# drivercontrols_adafruit_M0.net
KiCad netlist of a schematic drawn in EAGLE
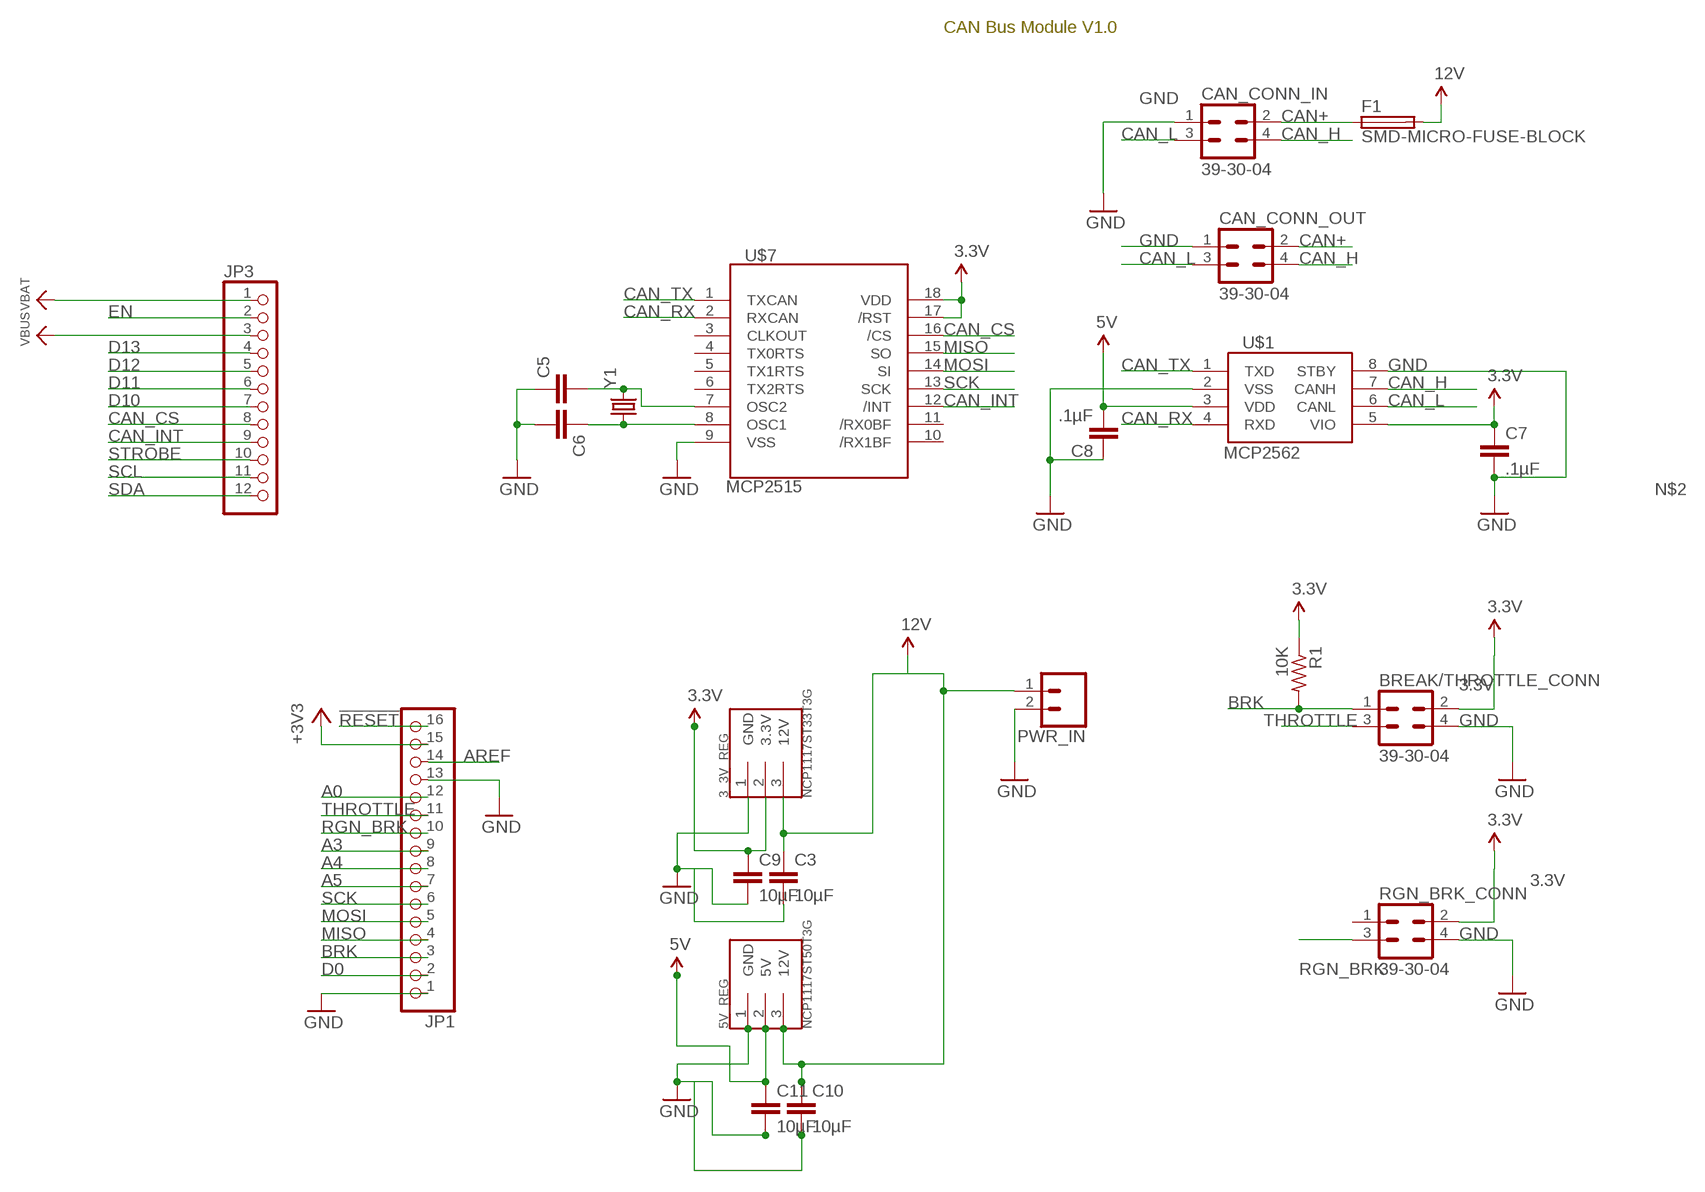
[diagram p0: schematic, sheet 1]

(export (version "E")
  (design (tool "Eeschema 10.0.6"))
  (components
    (comp (ref "3_3V_REG")
      (value "NCP1117ST33T3G")
      (footprint "eagle-import:SOT223")
      (libsource (lib "eagle-import") (part "NCP1117ST33T3G"))
    )
    (comp (ref "5V_REG")
      (value "NCP1117ST50T3G")
      (footprint "eagle-import:SOT223")
      (libsource (lib "eagle-import") (part "NCP1117ST50T3G"))
    )
    (comp (ref "BREAK/THROTTLE_CONN")
      (value "39-30-04")
      (footprint "eagle-import:39-30-_04_")
      (libsource (lib "eagle-import") (part "39-30-?04?"))
    )
    (comp (ref "C3")
      (value "10µF")
      (footprint "eagle-import:0805")
      (libsource (lib "eagle-import") (part "CAP0805"))
    )
    (comp (ref "C5")
      (value "CAP0805")
      (footprint "eagle-import:0805")
      (libsource (lib "eagle-import") (part "CAP0805"))
    )
    (comp (ref "C6")
      (value "CAP0805")
      (footprint "eagle-import:0805")
      (libsource (lib "eagle-import") (part "CAP0805"))
    )
    (comp (ref "C7")
      (value ".1µF")
      (footprint "eagle-import:0805")
      (libsource (lib "eagle-import") (part "CAP0805"))
    )
    (comp (ref "C8")
      (value ".1µF")
      (footprint "eagle-import:0805")
      (libsource (lib "eagle-import") (part "CAP0805"))
    )
    (comp (ref "C9")
      (value "10µF")
      (footprint "eagle-import:0805")
      (libsource (lib "eagle-import") (part "CAP0805"))
    )
    (comp (ref "C10")
      (value "10µF")
      (footprint "eagle-import:0805")
      (libsource (lib "eagle-import") (part "CAP0805"))
    )
    (comp (ref "C11")
      (value "10µF")
      (footprint "eagle-import:0805")
      (libsource (lib "eagle-import") (part "CAP0805"))
    )
    (comp (ref "CAN_CONN_IN")
      (value "39-30-04")
      (footprint "eagle-import:39-30-_04_")
      (libsource (lib "eagle-import") (part "39-30-?04?"))
    )
    (comp (ref "CAN_CONN_OUT")
      (value "39-30-04")
      (footprint "eagle-import:39-30-_04_")
      (libsource (lib "eagle-import") (part "39-30-?04?"))
    )
    (comp (ref "F1")
      (value "SMD-MICRO-FUSE-BLOCK")
      (footprint "eagle-import:OMNIBLOK")
      (libsource (lib "eagle-import") (part "SMD-MICRO-FUSE-BLOCK"))
    )
    (comp (ref "JP1")
      (value "HEADER-1X16ROUND")
      (footprint "eagle-import:1X16_ROUND")
      (libsource (lib "eagle-import") (part "HEADER-1X16ROUND"))
    )
    (comp (ref "JP3")
      (value "HEADER-1X12")
      (footprint "eagle-import:1X12_ROUND")
      (libsource (lib "eagle-import") (part "HEADER-1X12"))
    )
    (comp (ref "PWR_IN")
      (value "CONN_02")
      (footprint "eagle-import:1X02")
      (libsource (lib "eagle-import") (part "CONN_02"))
    )
    (comp (ref "R1")
      (value "10K")
      (footprint "eagle-import:M0805")
      (libsource (lib "eagle-import") (part "R-US_M0805"))
    )
    (comp (ref "RGN_BRK_CONN")
      (value "39-30-04")
      (footprint "eagle-import:39-30-_04_")
      (libsource (lib "eagle-import") (part "39-30-?04?"))
    )
    (comp (ref "U$1")
      (value "MCP2562")
      (footprint "eagle-import:SOIC8")
      (libsource (lib "eagle-import") (part "MCP2562"))
    )
    (comp (ref "U$7")
      (value "MCP2515")
      (footprint "eagle-import:SO-18W")
      (libsource (lib "eagle-import") (part "MCP2515"))
    )
    (comp (ref "Y1")
      (value "CRYSTALHC49US")
      (footprint "eagle-import:HC49US")
      (libsource (lib "eagle-import") (part "CRYSTALHC49US"))
    )
  )
  (nets
    (net (code "1") (name "+3V3") (class "Default")
      (node (ref "JP1") (pin "15") (pinfunction "15_15") (pintype "passive"))
    )
    (net (code "2") (name "/A0") (class "Default")
      (node (ref "JP1") (pin "12") (pinfunction "12_12") (pintype "passive"))
    )
    (net (code "3") (name "/A3") (class "Default")
      (node (ref "JP1") (pin "9") (pinfunction "9_9") (pintype "passive"))
    )
    (net (code "4") (name "/A4") (class "Default")
      (node (ref "JP1") (pin "8") (pinfunction "8_8") (pintype "passive"))
    )
    (net (code "5") (name "/A5") (class "Default")
      (node (ref "JP1") (pin "7") (pinfunction "7_7") (pintype "passive"))
    )
    (net (code "6") (name "/AREF") (class "Default")
      (node (ref "JP1") (pin "14") (pinfunction "14_14") (pintype "passive"))
    )
    (net (code "7") (name "/BRK") (class "Default")
      (node (ref "BREAK/THROTTLE_CONN") (pin "1") (pinfunction "1_1") (pintype "passive"))
      (node (ref "JP1") (pin "3") (pinfunction "3_3") (pintype "passive"))
      (node (ref "R1") (pin "2") (pinfunction "2_2") (pintype "passive"))
    )
    (net (code "8") (name "/CAN+") (class "Default")
      (node (ref "CAN_CONN_IN") (pin "2") (pinfunction "2_2") (pintype "passive"))
      (node (ref "CAN_CONN_OUT") (pin "2") (pinfunction "2_2") (pintype "passive"))
      (node (ref "F1") (pin "P$1") (pinfunction "1_P$1") (pintype "passive"))
    )
    (net (code "9") (name "/CAN_CS") (class "Default")
      (node (ref "JP3") (pin "8") (pinfunction "8_8") (pintype "passive"))
      (node (ref "U$7") (pin "16") (pinfunction "/CS_16") (pintype "bidirectional"))
    )
    (net (code "10") (name "/CAN_H") (class "Default")
      (node (ref "CAN_CONN_IN") (pin "4") (pinfunction "4_4") (pintype "passive"))
      (node (ref "CAN_CONN_OUT") (pin "4") (pinfunction "4_4") (pintype "passive"))
      (node (ref "U$1") (pin "7") (pinfunction "CANH_7") (pintype "bidirectional"))
    )
    (net (code "11") (name "/CAN_INT") (class "Default")
      (node (ref "JP3") (pin "9") (pinfunction "9_9") (pintype "passive"))
      (node (ref "U$7") (pin "12") (pinfunction "/INT_12") (pintype "bidirectional"))
    )
    (net (code "12") (name "/CAN_L") (class "Default")
      (node (ref "CAN_CONN_IN") (pin "3") (pinfunction "3_3") (pintype "passive"))
      (node (ref "CAN_CONN_OUT") (pin "3") (pinfunction "3_3") (pintype "passive"))
      (node (ref "U$1") (pin "6") (pinfunction "CANL_6") (pintype "bidirectional"))
    )
    (net (code "13") (name "/CAN_RX") (class "Default")
      (node (ref "U$1") (pin "4") (pinfunction "RXD_4") (pintype "bidirectional"))
      (node (ref "U$7") (pin "2") (pinfunction "RXCAN_2") (pintype "bidirectional"))
    )
    (net (code "14") (name "/CAN_TX") (class "Default")
      (node (ref "U$1") (pin "1") (pinfunction "TXD_1") (pintype "bidirectional"))
      (node (ref "U$7") (pin "1") (pinfunction "TXCAN_1") (pintype "bidirectional"))
    )
    (net (code "15") (name "/D0") (class "Default")
      (node (ref "JP1") (pin "2") (pinfunction "2_2") (pintype "passive"))
    )
    (net (code "16") (name "/D10") (class "Default")
      (node (ref "JP3") (pin "7") (pinfunction "7_7") (pintype "passive"))
    )
    (net (code "17") (name "/D11") (class "Default")
      (node (ref "JP3") (pin "6") (pinfunction "6_6") (pintype "passive"))
    )
    (net (code "18") (name "/D12") (class "Default")
      (node (ref "JP3") (pin "5") (pinfunction "5_5") (pintype "passive"))
    )
    (net (code "19") (name "/D13") (class "Default")
      (node (ref "JP3") (pin "4") (pinfunction "4_4") (pintype "passive"))
    )
    (net (code "20") (name "/EN") (class "Default")
      (node (ref "JP3") (pin "2") (pinfunction "2_2") (pintype "passive"))
    )
    (net (code "21") (name "/MISO") (class "Default")
      (node (ref "JP1") (pin "4") (pinfunction "4_4") (pintype "passive"))
      (node (ref "U$7") (pin "15") (pinfunction "SO_15") (pintype "bidirectional"))
    )
    (net (code "22") (name "/MOSI") (class "Default")
      (node (ref "JP1") (pin "5") (pinfunction "5_5") (pintype "passive"))
      (node (ref "U$7") (pin "14") (pinfunction "SI_14") (pintype "bidirectional"))
    )
    (net (code "23") (name "/RGN_BRK") (class "Default")
      (node (ref "JP1") (pin "10") (pinfunction "10_10") (pintype "passive"))
      (node (ref "RGN_BRK_CONN") (pin "3") (pinfunction "3_3") (pintype "passive"))
    )
    (net (code "24") (name "/SCK") (class "Default")
      (node (ref "JP1") (pin "6") (pinfunction "6_6") (pintype "passive"))
      (node (ref "U$7") (pin "13") (pinfunction "SCK_13") (pintype "bidirectional"))
    )
    (net (code "25") (name "/SCL") (class "Default")
      (node (ref "JP3") (pin "11") (pinfunction "11_11") (pintype "passive"))
    )
    (net (code "26") (name "/SDA") (class "Default")
      (node (ref "JP3") (pin "12") (pinfunction "12_12") (pintype "passive"))
    )
    (net (code "27") (name "/STROBE") (class "Default")
      (node (ref "JP3") (pin "10") (pinfunction "10_10") (pintype "passive"))
    )
    (net (code "28") (name "/THROTTLE") (class "Default")
      (node (ref "BREAK/THROTTLE_CONN") (pin "3") (pinfunction "3_3") (pintype "passive"))
      (node (ref "JP1") (pin "11") (pinfunction "11_11") (pintype "passive"))
    )
    (net (code "29") (name "/~{RESET}") (class "Default")
      (node (ref "JP1") (pin "16") (pinfunction "16_16") (pintype "passive"))
    )
    (net (code "30") (name "3.3V") (class "Default")
      (node (ref "3_3V_REG") (pin "2") (pinfunction "3.3V_2") (pintype "bidirectional"))
      (node (ref "BREAK/THROTTLE_CONN") (pin "2") (pinfunction "2_2") (pintype "passive"))
      (node (ref "C7") (pin "1") (pinfunction "1_1") (pintype "passive"))
      (node (ref "C9") (pin "1") (pinfunction "1_1") (pintype "passive"))
      (node (ref "R1") (pin "1") (pinfunction "1_1") (pintype "passive"))
      (node (ref "RGN_BRK_CONN") (pin "2") (pinfunction "2_2") (pintype "passive"))
      (node (ref "U$1") (pin "5") (pinfunction "VIO_5") (pintype "bidirectional"))
      (node (ref "U$7") (pin "17") (pinfunction "/RST_17") (pintype "bidirectional"))
      (node (ref "U$7") (pin "18") (pinfunction "VDD_18") (pintype "bidirectional"))
    )
    (net (code "31") (name "5V") (class "Default")
      (node (ref "5V_REG") (pin "2") (pinfunction "5V_2") (pintype "bidirectional"))
      (node (ref "C11") (pin "1") (pinfunction "1_1") (pintype "passive"))
      (node (ref "C8") (pin "2") (pinfunction "2_2") (pintype "passive"))
      (node (ref "U$1") (pin "3") (pinfunction "VDD_3") (pintype "bidirectional"))
    )
    (net (code "32") (name "12V") (class "Default")
      (node (ref "3_3V_REG") (pin "3") (pinfunction "12V_3") (pintype "bidirectional"))
      (node (ref "5V_REG") (pin "3") (pinfunction "12V_3") (pintype "bidirectional"))
      (node (ref "C10") (pin "1") (pinfunction "1_1") (pintype "passive"))
      (node (ref "C3") (pin "1") (pinfunction "1_1") (pintype "passive"))
      (node (ref "F1") (pin "P$2") (pinfunction "2_P$2") (pintype "passive"))
      (node (ref "PWR_IN") (pin "1") (pinfunction "1_1") (pintype "passive"))
    )
    (net (code "33") (name "GND") (class "Default")
      (node (ref "3_3V_REG") (pin "1") (pinfunction "GND_1") (pintype "bidirectional"))
      (node (ref "5V_REG") (pin "1") (pinfunction "GND_1") (pintype "bidirectional"))
      (node (ref "BREAK/THROTTLE_CONN") (pin "4") (pinfunction "4_4") (pintype "passive"))
      (node (ref "C10") (pin "2") (pinfunction "2_2") (pintype "passive"))
      (node (ref "C11") (pin "2") (pinfunction "2_2") (pintype "passive"))
      (node (ref "C3") (pin "2") (pinfunction "2_2") (pintype "passive"))
      (node (ref "C5") (pin "1") (pinfunction "1_1") (pintype "passive"))
      (node (ref "C6") (pin "2") (pinfunction "2_2") (pintype "passive"))
      (node (ref "C7") (pin "2") (pinfunction "2_2") (pintype "passive"))
      (node (ref "C8") (pin "1") (pinfunction "1_1") (pintype "passive"))
      (node (ref "C9") (pin "2") (pinfunction "2_2") (pintype "passive"))
      (node (ref "CAN_CONN_IN") (pin "1") (pinfunction "1_1") (pintype "passive"))
      (node (ref "CAN_CONN_OUT") (pin "1") (pinfunction "1_1") (pintype "passive"))
      (node (ref "JP1") (pin "1") (pinfunction "1_1") (pintype "passive"))
      (node (ref "JP1") (pin "13") (pinfunction "13_13") (pintype "passive"))
      (node (ref "PWR_IN") (pin "2") (pinfunction "2_2") (pintype "passive"))
      (node (ref "RGN_BRK_CONN") (pin "4") (pinfunction "4_4") (pintype "passive"))
      (node (ref "U$1") (pin "2") (pinfunction "VSS_2") (pintype "bidirectional"))
      (node (ref "U$1") (pin "8") (pinfunction "STBY_8") (pintype "bidirectional"))
      (node (ref "U$7") (pin "9") (pinfunction "VSS_9") (pintype "bidirectional"))
    )
    (net (code "34") (name "Net-(U$7-OSC1)") (class "Default")
      (node (ref "C6") (pin "1") (pinfunction "1_1") (pintype "passive"))
      (node (ref "U$7") (pin "8") (pinfunction "OSC1_8") (pintype "bidirectional"))
      (node (ref "Y1") (pin "1") (pinfunction "1_1") (pintype "passive"))
    )
    (net (code "35") (name "Net-(U$7-OSC2)") (class "Default")
      (node (ref "C5") (pin "2") (pinfunction "2_2") (pintype "passive"))
      (node (ref "U$7") (pin "7") (pinfunction "OSC2_7") (pintype "bidirectional"))
      (node (ref "Y1") (pin "2") (pinfunction "2_2") (pintype "passive"))
    )
    (net (code "36") (name "VBAT") (class "Default")
      (node (ref "JP3") (pin "1") (pinfunction "1_1") (pintype "passive"))
    )
    (net (code "37") (name "VBUS") (class "Default")
      (node (ref "JP3") (pin "3") (pinfunction "3_3") (pintype "passive"))
    )
    (net (code "38") (name "unconnected-(RGN_BRK_CONN-Pad1)") (class "Default")
      (node (ref "RGN_BRK_CONN") (pin "1") (pinfunction "1_1") (pintype "passive"))
    )
    (net (code "39") (name "unconnected-(U$7-CLKOUT-Pad3)") (class "Default")
      (node (ref "U$7") (pin "3") (pinfunction "CLKOUT_3") (pintype "bidirectional"))
    )
    (net (code "40") (name "unconnected-(U$7-TX0RTS-Pad4)") (class "Default")
      (node (ref "U$7") (pin "4") (pinfunction "TX0RTS_4") (pintype "bidirectional"))
    )
    (net (code "41") (name "unconnected-(U$7-TX1RTS-Pad5)") (class "Default")
      (node (ref "U$7") (pin "5") (pinfunction "TX1RTS_5") (pintype "bidirectional"))
    )
    (net (code "42") (name "unconnected-(U$7-TX2RTS-Pad6)") (class "Default")
      (node (ref "U$7") (pin "6") (pinfunction "TX2RTS_6") (pintype "bidirectional"))
    )
    (net (code "43") (name "unconnected-(U$7-{slash}RX0BF-Pad11)") (class "Default")
      (node (ref "U$7") (pin "11") (pinfunction "/RX0BF_11") (pintype "bidirectional"))
    )
    (net (code "44") (name "unconnected-(U$7-{slash}RX1BF-Pad10)") (class "Default")
      (node (ref "U$7") (pin "10") (pinfunction "/RX1BF_10") (pintype "bidirectional"))
    )
  )
)
